# 06-_-.net
KiCad netlist of a schematic drawn in Altium Designer
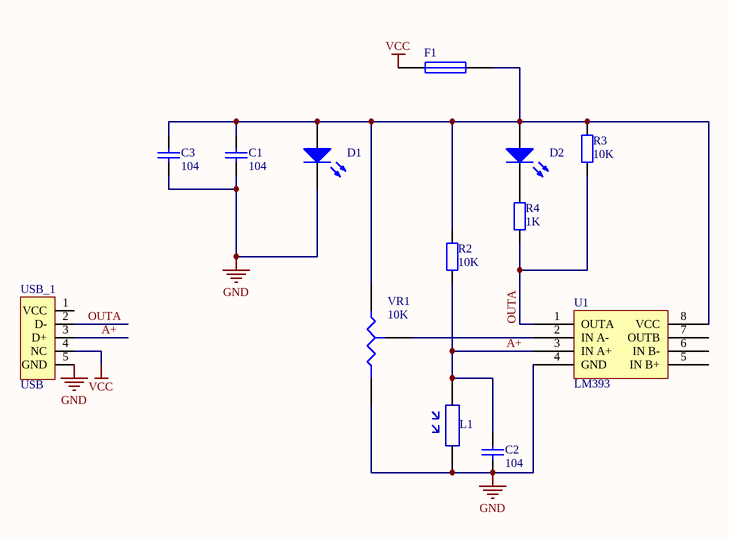
[diagram p0: 06-光敏传感器模块-原理图.SchDoc]

(export (version "E")
  (design (tool "Eeschema 10.0.6"))
  (components
    (comp (ref "C1")
      (value "104")
      (footprint "0805")
      (description "Capacitor (Semiconductor SIM Model)")
      (fields (field (name "Comment") "Cap Semi") (field (name "PUBLISHER") "Altium Limited"))
      (libsource (lib "Miscellaneous Devices") (part "Cap Semi"))
    )
    (comp (ref "C2")
      (value "104")
      (footprint "0805")
      (description "Capacitor (Semiconductor SIM Model)")
      (fields (field (name "Comment") "Cap Semi") (field (name "PUBLISHER") "Altium Limited"))
      (libsource (lib "Miscellaneous Devices") (part "Cap Semi"))
    )
    (comp (ref "C3")
      (value "104")
      (footprint "0805")
      (description "Capacitor (Semiconductor SIM Model)")
      (fields (field (name "Comment") "Cap Semi") (field (name "PUBLISHER") "Altium Limited"))
      (libsource (lib "Miscellaneous Devices") (part "Cap Semi"))
    )
    (comp (ref "D1")
      (value "LED0")
      (footprint "0805")
      (description "Typical INFRARED GaAs LED")
      (fields (field (name "PUBLISHER") "Altium Limited"))
      (libsource (lib "Miscellaneous Devices") (part "LED0"))
    )
    (comp (ref "D2")
      (value "LED0")
      (footprint "0805")
      (description "Typical INFRARED GaAs LED")
      (fields (field (name "PUBLISHER") "Altium Limited"))
      (libsource (lib "Miscellaneous Devices") (part "LED0"))
    )
    (comp (ref "F1")
      (value "Fuse 1")
      (footprint "Fuse")
      (description "Fuse")
      (fields (field (name "PUBLISHER") "Altium Limited"))
      (libsource (lib "Miscellaneous Devices") (part "Fuse 1"))
    )
    (comp (ref "L1") (value "light_resistor") (footprint "light") (libsource (lib "原理图库") (part "light")))
    (comp (ref "R2")
      (value "10K")
      (footprint "0805")
      (description "Resistor")
      (fields (field (name "Comment") "Res2") (field (name "PUBLISHER") "Altium Limited"))
      (libsource (lib "Miscellaneous Devices") (part "Res2"))
    )
    (comp (ref "R3")
      (value "10K")
      (footprint "0805")
      (description "Resistor")
      (fields (field (name "Comment") "Res2") (field (name "PUBLISHER") "Altium Limited"))
      (libsource (lib "Miscellaneous Devices") (part "Res2"))
    )
    (comp (ref "R4")
      (value "1K")
      (footprint "0805")
      (description "Resistor")
      (fields (field (name "Comment") "Res2") (field (name "PUBLISHER") "Altium Limited"))
      (libsource (lib "Miscellaneous Devices") (part "Res2"))
    )
    (comp (ref "U1") (value "LM393") (footprint "SOP-8") (libsource (lib "原理图库") (part "LM393")))
    (comp (ref "USB_1") (value "USB") (footprint "USB/SM0.8-6H5") (libsource (lib "原理图库") (part "USB5")))
    (comp (ref "VR1")
      (value "10K")
      (footprint "VR")
      (description "Tapped Resistor")
      (fields (field (name "Comment") "Res Tap") (field (name "PUBLISHER") "Altium Limited"))
      (libsource (lib "Miscellaneous Devices") (part "Res Tap"))
    )
  )
  (nets
    (net (code "1") (name "/A+") (class "Default")
      (node (ref "C2") (pin "2") (pinfunction "2_2") (pintype "passive"))
      (node (ref "L1") (pin "1") (pinfunction "1_1") (pintype "passive"))
      (node (ref "R2") (pin "1") (pinfunction "1_1") (pintype "passive"))
      (node (ref "U1") (pin "3") (pinfunction "IN_A+_3") (pintype "passive"))
      (node (ref "USB_1") (pin "3") (pinfunction "D+_3") (pintype "passive"))
    )
    (net (code "2") (name "/OUTA") (class "Default")
      (node (ref "R3") (pin "1") (pinfunction "1_1") (pintype "passive"))
      (node (ref "R4") (pin "1") (pinfunction "1_1") (pintype "passive"))
      (node (ref "U1") (pin "1") (pinfunction "OUTA_1") (pintype "passive"))
      (node (ref "USB_1") (pin "2") (pinfunction "D-_2") (pintype "passive"))
    )
    (net (code "3") (name "GND") (class "Default")
      (node (ref "C1") (pin "1") (pinfunction "1_1") (pintype "passive"))
      (node (ref "C2") (pin "1") (pinfunction "1_1") (pintype "passive"))
      (node (ref "C3") (pin "1") (pinfunction "1_1") (pintype "passive"))
      (node (ref "D1") (pin "2") (pinfunction "K_2") (pintype "passive"))
      (node (ref "L1") (pin "2") (pinfunction "2_2") (pintype "passive"))
      (node (ref "U1") (pin "4") (pinfunction "GND_4") (pintype "passive"))
      (node (ref "USB_1") (pin "5") (pinfunction "GND_5") (pintype "passive"))
      (node (ref "VR1") (pin "2") (pinfunction "B_2") (pintype "passive"))
    )
    (net (code "4") (name "Net-(D1-A)") (class "Default")
      (node (ref "C1") (pin "2") (pinfunction "2_2") (pintype "passive"))
      (node (ref "C3") (pin "2") (pinfunction "2_2") (pintype "passive"))
      (node (ref "D1") (pin "1") (pinfunction "A_1") (pintype "passive"))
      (node (ref "D2") (pin "1") (pinfunction "A_1") (pintype "passive"))
      (node (ref "F1") (pin "1") (pinfunction "1_1") (pintype "passive"))
      (node (ref "R2") (pin "2") (pinfunction "2_2") (pintype "passive"))
      (node (ref "R3") (pin "2") (pinfunction "2_2") (pintype "passive"))
      (node (ref "U1") (pin "8") (pinfunction "VCC_8") (pintype "passive"))
      (node (ref "VR1") (pin "1") (pinfunction "A_1") (pintype "passive"))
    )
    (net (code "5") (name "Net-(D2-K)") (class "Default")
      (node (ref "D2") (pin "2") (pinfunction "K_2") (pintype "passive"))
      (node (ref "R4") (pin "2") (pinfunction "2_2") (pintype "passive"))
    )
    (net (code "6") (name "Net-(U1-IN_A-)") (class "Default")
      (node (ref "U1") (pin "2") (pinfunction "IN_A-_2") (pintype "passive"))
      (node (ref "VR1") (pin "3") (pinfunction "TAP_3") (pintype "passive"))
    )
    (net (code "7") (name "VCC") (class "Default")
      (node (ref "F1") (pin "2") (pinfunction "2_2") (pintype "passive"))
      (node (ref "USB_1") (pin "4") (pinfunction "NC_4") (pintype "passive"))
    )
    (net (code "8") (name "unconnected-(U1-IN_B+-Pad5)") (class "Default")
      (node (ref "U1") (pin "5") (pinfunction "IN_B+_5") (pintype "passive"))
    )
    (net (code "9") (name "unconnected-(U1-IN_B--Pad6)") (class "Default")
      (node (ref "U1") (pin "6") (pinfunction "IN_B-_6") (pintype "passive"))
    )
    (net (code "10") (name "unconnected-(U1-OUTB-Pad7)") (class "Default")
      (node (ref "U1") (pin "7") (pinfunction "OUTB_7") (pintype "passive"))
    )
    (net (code "11") (name "unconnected-(USB_1-VCC-Pad1)") (class "Default")
      (node (ref "USB_1") (pin "1") (pinfunction "VCC_1") (pintype "passive"))
    )
  )
)
